# TelemetryBoard.net
KiCad netlist of a schematic drawn in Altium Designer
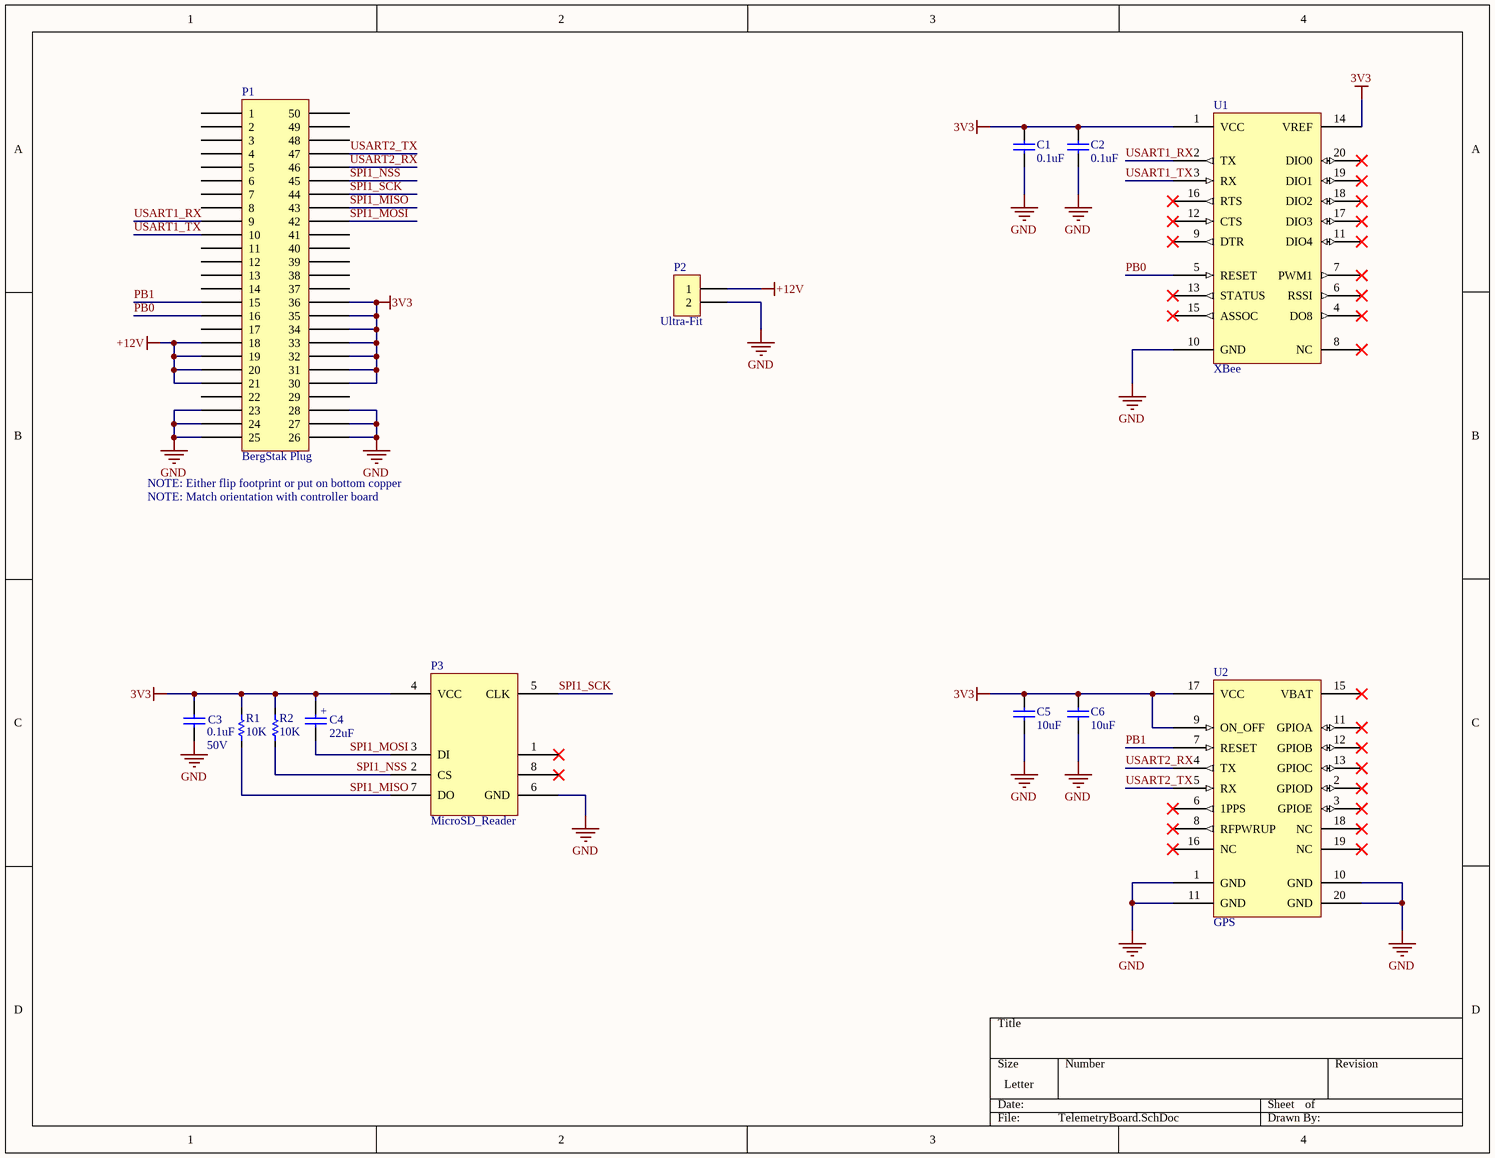
[diagram p0: TelemetryBoard.SchDoc]

(export (version "E")
  (design (tool "Eeschema 10.0.6"))
  (components
    (comp (ref "C1")
      (value "0.1uF")
      (footprint "0603")
      (description "0.10µF ±10% 50V Ceramic Capacitor X7R 0603 (1608 Metric)")
      (fields
        (field (name "MANUFACTURER") "AVX Corporation")
        (field (name "MANUFACTURERPARTNUMBER") "06035C104KAT2A")
      )
      (libsource (lib "Schematic Diagrams") (part "CAP CER 0.1UF 50V 10% X7R 0603"))
    )
    (comp (ref "C2")
      (value "0.1uF")
      (footprint "0603")
      (description "0.10µF ±10% 50V Ceramic Capacitor X7R 0603 (1608 Metric)")
      (fields
        (field (name "MANUFACTURER") "AVX Corporation")
        (field (name "MANUFACTURERPARTNUMBER") "06035C104KAT2A")
      )
      (libsource (lib "Schematic Diagrams") (part "CAP CER 0.1UF 50V 10% X7R 0603"))
    )
    (comp (ref "C3")
      (value "0.1uF")
      (footprint "CAPC1608X06N")
      (description "0.10µF ±10% 50V Ceramic Capacitor X7R 0603 (1608 Metric)")
      (fields
        (field (name "MANUFACTURER") "AVX Corporation")
        (field (name "MANUFACTURERPARTNUMBER") "06035C104KAT2A")
        (field (name "VOLTAGE") "50V")
      )
      (libsource (lib "Schematic Diagrams") (part "CAP CER 0.1UF 50V 10% X7R 0603"))
    )
    (comp (ref "C4")
      (value "22uF")
      (footprint "CAP TANT 22UF 6.3V 10% 1206")
      (description "22µF ±10% Molded Tantalum Capacitors 6.3V 1206 (3216 Metric) 3 Ohm")
      (fields (field (name "MANUFACTURER") "AVX Corporation") (field (name "VOLTAGE") "6.3V"))
      (libsource (lib "Schematic Diagrams") (part "CAP TANT 22UF 6.3V 10% 1206"))
    )
    (comp (ref "C5")
      (value "10uF")
      (footprint "0603")
      (description "10µF ±20% 25V Ceramic Capacitor X5R 0603 (1608 Metric)")
      (fields
        (field (name "MANUFACTURER") "Murata Electronics North America")
        (field (name "MANUFACTURERPARTNUMBER") "GRM188R61E106MA73D")
      )
      (libsource (lib "Schematic Diagrams") (part "CAP CER 10uF 25V 20% X5R 0603"))
    )
    (comp (ref "C6")
      (value "10uF")
      (footprint "0603")
      (description "10µF ±20% 25V Ceramic Capacitor X5R 0603 (1608 Metric)")
      (fields
        (field (name "MANUFACTURER") "Murata Electronics North America")
        (field (name "MANUFACTURERPARTNUMBER") "GRM188R61E106MA73D")
      )
      (libsource (lib "Schematic Diagrams") (part "CAP CER 10uF 25V 20% X5R 0603"))
    )
    (comp (ref "P1")
      (value "BergStak Plug")
      (footprint "609-5226-1-ND")
      (description "50 Position Connector Plug, Outer Shroud Contacts Surface Mount Gold")
      (libsource (lib "Schematic Diagrams") (part "BergStak 50 Position Connector Plug"))
    )
    (comp (ref "P2")
      (value "Ultra-Fit")
      (footprint "WM11673-ND")
      (description "2 Positions Header, Shrouded Connector 0.138\" (3.50mm) Through Hole Gold")
      (libsource (lib "Schematic Diagrams") (part "2 Position Ultra-Fit Connector"))
    )
    (comp (ref "P3")
      (value "MicroSD_Reader")
      (footprint "MicroSD_reader")
      (description "CONN MICRO SD CARD PUSH-PULL R/A")
      (libsource (lib "Schematic Diagrams") (part "MicroSD_Reader"))
    )
    (comp (ref "R1")
      (value "10K")
      (footprint "RESC1608X06N")
      (description "RES SMD 10K OHM 1% 1/10W 0603")
      (fields (field (name "MANUFACTURE PART NUMBER") "RC0603FR-0710KL") (field (name "TOLERANCE") "1%"))
      (libsource (lib "Schematic Diagrams") (part "RES SMD 10K OHM 1% 1/10W 0603"))
    )
    (comp (ref "R2")
      (value "10K")
      (footprint "RESC1608X06N")
      (description "RES SMD 10K OHM 1% 1/10W 0603")
      (fields (field (name "MANUFACTURE PART NUMBER") "RC0603FR-0710KL") (field (name "TOLERANCE") "1%"))
      (libsource (lib "Schematic Diagrams") (part "RES SMD 10K OHM 1% 1/10W 0603"))
    )
    (comp (ref "U1")
      (value "XBee")
      (footprint "XBee-PRO")
      (libsource (lib "Schematic Diagrams") (part "XBee"))
    )
    (comp (ref "U2")
      (value "GPS")
      (footprint "EVM-GPS-F4")
      (description "GPS Module")
      (libsource (lib "Schematic Diagrams") (part "GPS"))
    )
  )
  (nets
    (net (code "1") (name "+12V") (class "Default")
      (node (ref "P1") (pin "18") (pinfunction "18_18") (pintype "passive"))
      (node (ref "P1") (pin "19") (pinfunction "19_19") (pintype "passive"))
      (node (ref "P1") (pin "20") (pinfunction "20_20") (pintype "passive"))
      (node (ref "P1") (pin "21") (pinfunction "21_21") (pintype "passive"))
      (node (ref "P2") (pin "1") (pinfunction "1_1") (pintype "passive"))
    )
    (net (code "2") (name "/PB0") (class "Default")
      (node (ref "P1") (pin "16") (pinfunction "16_16") (pintype "passive"))
      (node (ref "U1") (pin "5") (pinfunction "RESET_5") (pintype "input"))
    )
    (net (code "3") (name "/PB1") (class "Default")
      (node (ref "P1") (pin "15") (pinfunction "15_15") (pintype "passive"))
      (node (ref "U2") (pin "7") (pinfunction "RESET_7") (pintype "input"))
    )
    (net (code "4") (name "/SPI1_MISO") (class "Default")
      (node (ref "P1") (pin "43") (pinfunction "43_43") (pintype "passive"))
      (node (ref "P3") (pin "7") (pinfunction "DO_7") (pintype "passive"))
      (node (ref "R1") (pin "1") (pinfunction "1_1") (pintype "passive"))
    )
    (net (code "5") (name "/SPI1_MOSI") (class "Default")
      (node (ref "C4") (pin "1") (pinfunction "1_1") (pintype "passive"))
      (node (ref "P1") (pin "42") (pinfunction "42_42") (pintype "passive"))
      (node (ref "P3") (pin "3") (pinfunction "DI_3") (pintype "passive"))
    )
    (net (code "6") (name "/SPI1_NSS") (class "Default")
      (node (ref "P1") (pin "45") (pinfunction "45_45") (pintype "passive"))
      (node (ref "P3") (pin "2") (pinfunction "CS_2") (pintype "passive"))
      (node (ref "R2") (pin "1") (pinfunction "1_1") (pintype "passive"))
    )
    (net (code "7") (name "/SPI1_SCK") (class "Default")
      (node (ref "P1") (pin "44") (pinfunction "44_44") (pintype "passive"))
      (node (ref "P3") (pin "5") (pinfunction "CLK_5") (pintype "passive"))
    )
    (net (code "8") (name "/USART1_RX") (class "Default")
      (node (ref "P1") (pin "9") (pinfunction "9_9") (pintype "passive"))
      (node (ref "U1") (pin "2") (pinfunction "TX_2") (pintype "output"))
    )
    (net (code "9") (name "/USART1_TX") (class "Default")
      (node (ref "P1") (pin "10") (pinfunction "10_10") (pintype "passive"))
      (node (ref "U1") (pin "3") (pinfunction "RX_3") (pintype "input"))
    )
    (net (code "10") (name "/USART2_RX") (class "Default")
      (node (ref "P1") (pin "46") (pinfunction "46_46") (pintype "passive"))
      (node (ref "U2") (pin "4") (pinfunction "TX_4") (pintype "output"))
    )
    (net (code "11") (name "/USART2_TX") (class "Default")
      (node (ref "P1") (pin "47") (pinfunction "47_47") (pintype "passive"))
      (node (ref "U2") (pin "5") (pinfunction "RX_5") (pintype "input"))
    )
    (net (code "12") (name "3V3") (class "Default")
      (node (ref "C1") (pin "2") (pinfunction "2_2") (pintype "passive"))
      (node (ref "C2") (pin "2") (pinfunction "2_2") (pintype "passive"))
      (node (ref "C3") (pin "2") (pinfunction "2_2") (pintype "passive"))
      (node (ref "C4") (pin "2") (pinfunction "2_2") (pintype "passive"))
      (node (ref "C5") (pin "2") (pinfunction "2_2") (pintype "passive"))
      (node (ref "C6") (pin "2") (pinfunction "2_2") (pintype "passive"))
      (node (ref "P1") (pin "30") (pinfunction "30_30") (pintype "passive"))
      (node (ref "P1") (pin "31") (pinfunction "31_31") (pintype "passive"))
      (node (ref "P1") (pin "32") (pinfunction "32_32") (pintype "passive"))
      (node (ref "P1") (pin "33") (pinfunction "33_33") (pintype "passive"))
      (node (ref "P1") (pin "34") (pinfunction "34_34") (pintype "passive"))
      (node (ref "P1") (pin "35") (pinfunction "35_35") (pintype "passive"))
      (node (ref "P1") (pin "36") (pinfunction "36_36") (pintype "passive"))
      (node (ref "P3") (pin "4") (pinfunction "VCC_4") (pintype "power_in"))
      (node (ref "R1") (pin "2") (pinfunction "2_2") (pintype "passive"))
      (node (ref "R2") (pin "2") (pinfunction "2_2") (pintype "passive"))
      (node (ref "U1") (pin "1") (pinfunction "VCC_1") (pintype "power_in"))
      (node (ref "U1") (pin "14") (pinfunction "VREF_14") (pintype "power_in"))
      (node (ref "U2") (pin "17") (pinfunction "VCC_17") (pintype "power_in"))
      (node (ref "U2") (pin "9") (pinfunction "ON_OFF_9") (pintype "input"))
    )
    (net (code "13") (name "GND") (class "Default")
      (node (ref "C1") (pin "1") (pinfunction "1_1") (pintype "passive"))
      (node (ref "C2") (pin "1") (pinfunction "1_1") (pintype "passive"))
      (node (ref "C3") (pin "1") (pinfunction "1_1") (pintype "passive"))
      (node (ref "C5") (pin "1") (pinfunction "1_1") (pintype "passive"))
      (node (ref "C6") (pin "1") (pinfunction "1_1") (pintype "passive"))
      (node (ref "P1") (pin "23") (pinfunction "23_23") (pintype "passive"))
      (node (ref "P1") (pin "24") (pinfunction "24_24") (pintype "passive"))
      (node (ref "P1") (pin "25") (pinfunction "25_25") (pintype "passive"))
      (node (ref "P1") (pin "26") (pinfunction "26_26") (pintype "passive"))
      (node (ref "P1") (pin "27") (pinfunction "27_27") (pintype "passive"))
      (node (ref "P1") (pin "28") (pinfunction "28_28") (pintype "passive"))
      (node (ref "P2") (pin "2") (pinfunction "2_2") (pintype "passive"))
      (node (ref "P3") (pin "6") (pinfunction "GND_6") (pintype "power_in"))
      (node (ref "U1") (pin "10") (pinfunction "GND_10") (pintype "passive"))
      (node (ref "U2") (pin "1") (pinfunction "GND_1") (pintype "power_in"))
      (node (ref "U2") (pin "10") (pinfunction "GND_10") (pintype "power_in"))
      (node (ref "U2") (pin "11") (pinfunction "GND_11") (pintype "power_in"))
      (node (ref "U2") (pin "20") (pinfunction "GND_20") (pintype "power_in"))
    )
    (net (code "14") (name "unconnected-(P1-Pad1)") (class "Default")
      (node (ref "P1") (pin "1") (pinfunction "1_1") (pintype "passive"))
    )
    (net (code "15") (name "unconnected-(P1-Pad2)") (class "Default")
      (node (ref "P1") (pin "2") (pinfunction "2_2") (pintype "passive"))
    )
    (net (code "16") (name "unconnected-(P1-Pad3)") (class "Default")
      (node (ref "P1") (pin "3") (pinfunction "3_3") (pintype "passive"))
    )
    (net (code "17") (name "unconnected-(P1-Pad4)") (class "Default")
      (node (ref "P1") (pin "4") (pinfunction "4_4") (pintype "passive"))
    )
    (net (code "18") (name "unconnected-(P1-Pad5)") (class "Default")
      (node (ref "P1") (pin "5") (pinfunction "5_5") (pintype "passive"))
    )
    (net (code "19") (name "unconnected-(P1-Pad6)") (class "Default")
      (node (ref "P1") (pin "6") (pinfunction "6_6") (pintype "passive"))
    )
    (net (code "20") (name "unconnected-(P1-Pad7)") (class "Default")
      (node (ref "P1") (pin "7") (pinfunction "7_7") (pintype "passive"))
    )
    (net (code "21") (name "unconnected-(P1-Pad8)") (class "Default")
      (node (ref "P1") (pin "8") (pinfunction "8_8") (pintype "passive"))
    )
    (net (code "22") (name "unconnected-(P1-Pad11)") (class "Default")
      (node (ref "P1") (pin "11") (pinfunction "11_11") (pintype "passive"))
    )
    (net (code "23") (name "unconnected-(P1-Pad12)") (class "Default")
      (node (ref "P1") (pin "12") (pinfunction "12_12") (pintype "passive"))
    )
    (net (code "24") (name "unconnected-(P1-Pad13)") (class "Default")
      (node (ref "P1") (pin "13") (pinfunction "13_13") (pintype "passive"))
    )
    (net (code "25") (name "unconnected-(P1-Pad14)") (class "Default")
      (node (ref "P1") (pin "14") (pinfunction "14_14") (pintype "passive"))
    )
    (net (code "26") (name "unconnected-(P1-Pad17)") (class "Default")
      (node (ref "P1") (pin "17") (pinfunction "17_17") (pintype "passive"))
    )
    (net (code "27") (name "unconnected-(P1-Pad22)") (class "Default")
      (node (ref "P1") (pin "22") (pinfunction "22_22") (pintype "passive"))
    )
    (net (code "28") (name "unconnected-(P1-Pad29)") (class "Default")
      (node (ref "P1") (pin "29") (pinfunction "29_29") (pintype "passive"))
    )
    (net (code "29") (name "unconnected-(P1-Pad37)") (class "Default")
      (node (ref "P1") (pin "37") (pinfunction "37_37") (pintype "passive"))
    )
    (net (code "30") (name "unconnected-(P1-Pad38)") (class "Default")
      (node (ref "P1") (pin "38") (pinfunction "38_38") (pintype "passive"))
    )
    (net (code "31") (name "unconnected-(P1-Pad39)") (class "Default")
      (node (ref "P1") (pin "39") (pinfunction "39_39") (pintype "passive"))
    )
    (net (code "32") (name "unconnected-(P1-Pad40)") (class "Default")
      (node (ref "P1") (pin "40") (pinfunction "40_40") (pintype "passive"))
    )
    (net (code "33") (name "unconnected-(P1-Pad41)") (class "Default")
      (node (ref "P1") (pin "41") (pinfunction "41_41") (pintype "passive"))
    )
    (net (code "34") (name "unconnected-(P1-Pad48)") (class "Default")
      (node (ref "P1") (pin "48") (pinfunction "48_48") (pintype "passive"))
    )
    (net (code "35") (name "unconnected-(P1-Pad49)") (class "Default")
      (node (ref "P1") (pin "49") (pinfunction "49_49") (pintype "passive"))
    )
    (net (code "36") (name "unconnected-(P1-Pad50)") (class "Default")
      (node (ref "P1") (pin "50") (pinfunction "50_50") (pintype "passive"))
    )
    (net (code "37") (name "unconnected-(P3-Pad1)") (class "Default")
      (node (ref "P3") (pin "1") (pintype "passive+no_connect"))
    )
    (net (code "38") (name "unconnected-(P3-Pad8)") (class "Default")
      (node (ref "P3") (pin "8") (pintype "passive+no_connect"))
    )
    (net (code "39") (name "unconnected-(U1-ASSOC-Pad15)") (class "Default")
      (node (ref "U1") (pin "15") (pinfunction "ASSOC_15") (pintype "output+no_connect"))
    )
    (net (code "40") (name "unconnected-(U1-CTS-Pad12)") (class "Default")
      (node (ref "U1") (pin "12") (pinfunction "CTS_12") (pintype "input+no_connect"))
    )
    (net (code "41") (name "unconnected-(U1-DIO0-Pad20)") (class "Default")
      (node (ref "U1") (pin "20") (pinfunction "DIO0_20") (pintype "bidirectional+no_connect"))
    )
    (net (code "42") (name "unconnected-(U1-DIO1-Pad19)") (class "Default")
      (node (ref "U1") (pin "19") (pinfunction "DIO1_19") (pintype "bidirectional+no_connect"))
    )
    (net (code "43") (name "unconnected-(U1-DIO2-Pad18)") (class "Default")
      (node (ref "U1") (pin "18") (pinfunction "DIO2_18") (pintype "bidirectional+no_connect"))
    )
    (net (code "44") (name "unconnected-(U1-DIO3-Pad17)") (class "Default")
      (node (ref "U1") (pin "17") (pinfunction "DIO3_17") (pintype "bidirectional+no_connect"))
    )
    (net (code "45") (name "unconnected-(U1-DIO4-Pad11)") (class "Default")
      (node (ref "U1") (pin "11") (pinfunction "DIO4_11") (pintype "bidirectional+no_connect"))
    )
    (net (code "46") (name "unconnected-(U1-DO8-Pad4)") (class "Default")
      (node (ref "U1") (pin "4") (pinfunction "DO8_4") (pintype "output+no_connect"))
    )
    (net (code "47") (name "unconnected-(U1-DTR-Pad9)") (class "Default")
      (node (ref "U1") (pin "9") (pinfunction "DTR_9") (pintype "output+no_connect"))
    )
    (net (code "48") (name "unconnected-(U1-NC-Pad8)") (class "Default")
      (node (ref "U1") (pin "8") (pinfunction "NC_8") (pintype "passive+no_connect"))
    )
    (net (code "49") (name "unconnected-(U1-PWM1-Pad7)") (class "Default")
      (node (ref "U1") (pin "7") (pinfunction "PWM1_7") (pintype "output+no_connect"))
    )
    (net (code "50") (name "unconnected-(U1-RSSI-Pad6)") (class "Default")
      (node (ref "U1") (pin "6") (pinfunction "RSSI_6") (pintype "output+no_connect"))
    )
    (net (code "51") (name "unconnected-(U1-RTS-Pad16)") (class "Default")
      (node (ref "U1") (pin "16") (pinfunction "RTS_16") (pintype "output+no_connect"))
    )
    (net (code "52") (name "unconnected-(U1-STATUS-Pad13)") (class "Default")
      (node (ref "U1") (pin "13") (pinfunction "STATUS_13") (pintype "output+no_connect"))
    )
    (net (code "53") (name "unconnected-(U2-1PPS-Pad6)") (class "Default")
      (node (ref "U2") (pin "6") (pinfunction "1PPS_6") (pintype "output+no_connect"))
    )
    (net (code "54") (name "unconnected-(U2-GPIOA-Pad11)") (class "Default")
      (node (ref "U2") (pin "11") (pinfunction "GPIOA_11") (pintype "bidirectional+no_connect"))
    )
    (net (code "55") (name "unconnected-(U2-GPIOB-Pad12)") (class "Default")
      (node (ref "U2") (pin "12") (pinfunction "GPIOB_12") (pintype "bidirectional+no_connect"))
    )
    (net (code "56") (name "unconnected-(U2-GPIOC-Pad13)") (class "Default")
      (node (ref "U2") (pin "13") (pinfunction "GPIOC_13") (pintype "bidirectional+no_connect"))
    )
    (net (code "57") (name "unconnected-(U2-GPIOD-Pad2)") (class "Default")
      (node (ref "U2") (pin "2") (pinfunction "GPIOD_2") (pintype "bidirectional+no_connect"))
    )
    (net (code "58") (name "unconnected-(U2-GPIOE-Pad3)") (class "Default")
      (node (ref "U2") (pin "3") (pinfunction "GPIOE_3") (pintype "bidirectional+no_connect"))
    )
    (net (code "59") (name "unconnected-(U2-NC-Pad16)") (class "Default")
      (node (ref "U2") (pin "16") (pinfunction "NC_16") (pintype "passive+no_connect"))
    )
    (net (code "60") (name "unconnected-(U2-NC-Pad18)") (class "Default")
      (node (ref "U2") (pin "18") (pinfunction "NC_18") (pintype "passive+no_connect"))
    )
    (net (code "61") (name "unconnected-(U2-NC-Pad19)") (class "Default")
      (node (ref "U2") (pin "19") (pinfunction "NC_19") (pintype "passive+no_connect"))
    )
    (net (code "62") (name "unconnected-(U2-RFPWRUP-Pad8)") (class "Default")
      (node (ref "U2") (pin "8") (pinfunction "RFPWRUP_8") (pintype "output+no_connect"))
    )
    (net (code "63") (name "unconnected-(U2-VBAT-Pad15)") (class "Default")
      (node (ref "U2") (pin "15") (pinfunction "VBAT_15") (pintype "power_in+no_connect"))
    )
  )
)
